# imu_ism330.net
KiCad netlist of a schematic drawn in Altium Designer
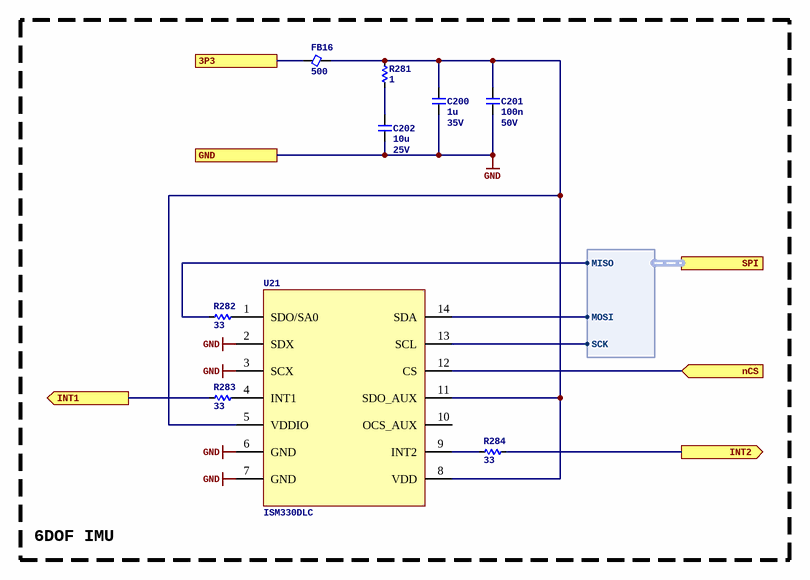
[diagram p0: imu_ism330.SchDoc]

(export (version "E")
  (design (tool "Eeschema 10.0.6"))
  (components
    (comp (ref "C200")
      (value "GMK107AB7105KAHT")
      (footprint "C0603")
      (fields
        (field (name "CAPACITANCE") "1u")
        (field (name "MANUFACTURER") "Taiyo Yuden")
        (field (name "VOLTAGE RATING") "35V")
      )
      (libsource (lib "database") (part "__template_cap"))
    )
    (comp (ref "C201")
      (value "CL05B104KB54PNC")
      (footprint "C0402")
      (fields
        (field (name "CAPACITANCE") "100n")
        (field (name "MANUFACTURER") "Samsung Electro-Mechanics")
        (field (name "VOLTAGE RATING") "50V")
      )
      (libsource (lib "database") (part "__template_cap"))
    )
    (comp (ref "C202")
      (value "CL21B106KAYQNNE")
      (footprint "C0805")
      (fields
        (field (name "CAPACITANCE") "10u")
        (field (name "MANUFACTURER") "Samsung Electro-Mechanics")
        (field (name "VOLTAGE RATING") "25V")
      )
      (libsource (lib "database") (part "__template_cap"))
    )
    (comp (ref "FB16")
      (value "BLM15AX601SN1D")
      (footprint "FB0402")
      (fields (field (name "MANUFACTURER") "Murata Electronics") (field (name "CURRENT RATING (MA)") "500"))
      (libsource (lib "database") (part "__template_fb"))
    )
    (comp (ref "R281")
      (value "1")
      (footprint "R0402")
      (fields
        (field (name "TOLERANCE") "1%")
        (field (name "MANUFACTURER PART NUMBER") "CRCW04021R00FKED")
        (field (name "MANUFACTURER") "Vishay Intertech")
      )
      (libsource (lib "database") (part "__template_resistor"))
    )
    (comp (ref "R282")
      (value "33")
      (footprint "R0402")
      (fields
        (field (name "TOLERANCE") "1%")
        (field (name "MANUFACTURER PART NUMBER") "0402WGF330JTCE")
        (field (name "MANUFACTURER") "UNI-ROYAL(Uniroyal Elec)")
      )
      (libsource (lib "database") (part "__template_resistor"))
    )
    (comp (ref "R283")
      (value "33")
      (footprint "R0402")
      (fields
        (field (name "TOLERANCE") "1%")
        (field (name "MANUFACTURER PART NUMBER") "0402WGF330JTCE")
        (field (name "MANUFACTURER") "UNI-ROYAL(Uniroyal Elec)")
      )
      (libsource (lib "database") (part "__template_resistor"))
    )
    (comp (ref "R284")
      (value "33")
      (footprint "R0402")
      (fields
        (field (name "TOLERANCE") "1%")
        (field (name "MANUFACTURER PART NUMBER") "0402WGF330JTCE")
        (field (name "MANUFACTURER") "UNI-ROYAL(Uniroyal Elec)")
      )
      (libsource (lib "database") (part "__template_resistor"))
    )
    (comp (ref "U21")
      (value "ISM330DLC")
      (footprint "ST_LGA-14L")
      (description "ST ACCELEROMETER/GYROSCOPE 3D 14LGA LOW POWER")
      (fields
        (field (name "MANUFACTURER PART NUMBER") "ISM330DLC")
        (field (name "MANUFACTURER") "ST Microelectronics")
      )
      (libsource (lib "SSCP") (part "IMU_ISM330DLC"))
    )
  )
  (nets
    (net (code "2") (name "/3P3") (class "Default") (node (ref "FB16") (pin "1") (pintype "passive")))
    (net (code "3") (name "/INT1") (class "Default") (node (ref "R283") (pin "1") (pintype "passive")))
    (net (code "4") (name "/INT2") (class "Default") (node (ref "R284") (pin "2") (pintype "passive")))
    (net (code "5") (name "/MISO") (class "Default") (node (ref "R282") (pin "1") (pintype "passive")))
    (net (code "6") (name "/MOSI") (class "Default")
      (node (ref "U21") (pin "14") (pinfunction "SDA_14") (pintype "passive"))
    )
    (net (code "7") (name "/SCK") (class "Default")
      (node (ref "U21") (pin "13") (pinfunction "SCL_13") (pintype "passive"))
    )
    (net (code "8") (name "/nCS") (class "Default")
      (node (ref "U21") (pin "12") (pinfunction "CS_12") (pintype "passive"))
    )
    (net (code "10") (name "GND") (class "Default")
      (node (ref "C200") (pin "2") (pintype "passive"))
      (node (ref "C201") (pin "2") (pintype "passive"))
      (node (ref "C202") (pin "2") (pintype "passive"))
      (node (ref "U21") (pin "2") (pinfunction "SDX_2") (pintype "passive"))
      (node (ref "U21") (pin "3") (pinfunction "SCX_3") (pintype "passive"))
      (node (ref "U21") (pin "6") (pinfunction "GND_6") (pintype "passive"))
      (node (ref "U21") (pin "7") (pinfunction "GND_7") (pintype "passive"))
    )
    (net (code "11") (name "Net-(C202-Pad1)") (class "Default")
      (node (ref "C202") (pin "1") (pintype "passive"))
      (node (ref "R281") (pin "1") (pintype "passive"))
    )
    (net (code "12") (name "Net-(U21-INT1)") (class "Default")
      (node (ref "R283") (pin "2") (pintype "passive"))
      (node (ref "U21") (pin "4") (pinfunction "INT1_4") (pintype "passive"))
    )
    (net (code "13") (name "Net-(U21-INT2)") (class "Default")
      (node (ref "R284") (pin "1") (pintype "passive"))
      (node (ref "U21") (pin "9") (pinfunction "INT2_9") (pintype "passive"))
    )
    (net (code "14") (name "Net-(U21-SDO_AUX)") (class "Default")
      (node (ref "C200") (pin "1") (pintype "passive"))
      (node (ref "C201") (pin "1") (pintype "passive"))
      (node (ref "FB16") (pin "2") (pintype "passive"))
      (node (ref "R281") (pin "2") (pintype "passive"))
      (node (ref "U21") (pin "11") (pinfunction "SDO_AUX_11") (pintype "passive"))
      (node (ref "U21") (pin "5") (pinfunction "VDDIO_5") (pintype "passive"))
      (node (ref "U21") (pin "8") (pinfunction "VDD_8") (pintype "passive"))
    )
    (net (code "15") (name "Net-(U21-SDO{slash}SA0)") (class "Default")
      (node (ref "R282") (pin "2") (pintype "passive"))
      (node (ref "U21") (pin "1") (pinfunction "SDO/SA0_1") (pintype "passive"))
    )
    (net (code "16") (name "unconnected-(U21-OCS_AUX-Pad10)") (class "Default")
      (node (ref "U21") (pin "10") (pinfunction "OCS_AUX_10") (pintype "passive"))
    )
  )
)
